# STM.net
KiCad netlist of a schematic drawn in Altium Designer
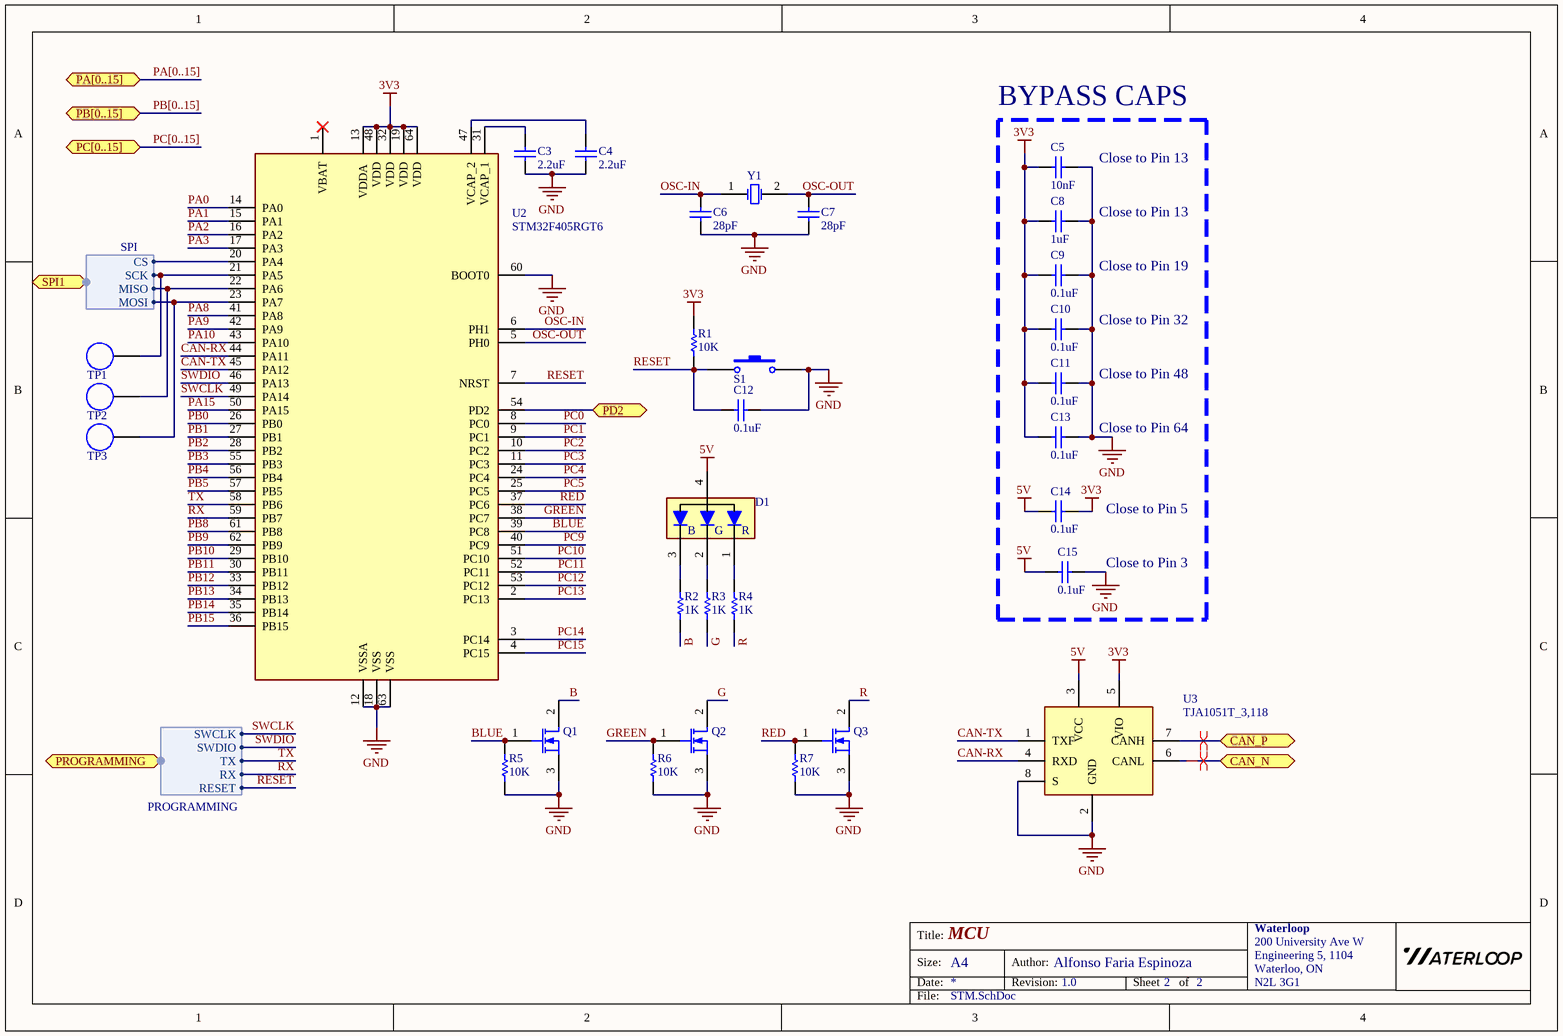
[diagram p0: STM.SchDoc]

(export (version "E")
  (design (tool "Eeschema 10.0.6"))
  (components
    (comp (ref "C3")
      (value "2.2uF")
      (footprint "0805 - Capacitor")
      (description "Nonpolarized Capacitor")
      (fields
        (field (name "MANUFACTURER") "Samsung")
        (field (name "MANUFACTURER PART NUMBER") "CL21B225KPFNNNE")
      )
      (libsource (lib "General") (part "Capacitor - Nonpolarized"))
    )
    (comp (ref "C4")
      (value "2.2uF")
      (footprint "0805 - Capacitor")
      (description "Nonpolarized Capacitor")
      (fields
        (field (name "MANUFACTURER") "Samsung")
        (field (name "MANUFACTURER PART NUMBER") "CL21B225KPFNNNE")
      )
      (libsource (lib "General") (part "Capacitor - Nonpolarized"))
    )
    (comp (ref "C5")
      (value "10nF")
      (footprint "0805 - Capacitor")
      (description "Nonpolarized Capacitor")
      (fields
        (field (name "MANUFACTURER") "Yageo")
        (field (name "MANUFACTURER PART NUMBER") "CC0805KRX7R9BB103")
      )
      (libsource (lib "General") (part "Capacitor - Nonpolarized"))
    )
    (comp (ref "C6")
      (value "28pF")
      (footprint "0805 - Capacitor")
      (description "Nonpolarized Capacitor")
      (fields
        (field (name "MANUFACTURER") "Samsung")
        (field (name "MANUFACTURER PART NUMBER") "CL21C270JCANNNC")
      )
      (libsource (lib "General") (part "Capacitor - Nonpolarized"))
    )
    (comp (ref "C7")
      (value "28pF")
      (footprint "0805 - Capacitor")
      (description "Nonpolarized Capacitor")
      (fields
        (field (name "MANUFACTURER") "Samsung")
        (field (name "MANUFACTURER PART NUMBER") "CL21C270JCANNNC")
      )
      (libsource (lib "General") (part "Capacitor - Nonpolarized"))
    )
    (comp (ref "C8")
      (value "1uF")
      (footprint "0805 - Capacitor")
      (description "Nonpolarized Capacitor")
      (fields
        (field (name "MANUFACTURER") "Yageo")
        (field (name "MANUFACTURER PART NUMBER") "CC0805KKX7R9BB105")
      )
      (libsource (lib "General") (part "Capacitor - Nonpolarized"))
    )
    (comp (ref "C9")
      (value "0.1uF")
      (footprint "0805 - Capacitor")
      (description "Nonpolarized Capacitor")
      (fields
        (field (name "MANUFACTURER") "Yageo")
        (field (name "MANUFACTURER PART NUMBER") "CC0805KRX7R9BB104")
      )
      (libsource (lib "General") (part "Capacitor - Nonpolarized"))
    )
    (comp (ref "C10")
      (value "0.1uF")
      (footprint "0805 - Capacitor")
      (description "Nonpolarized Capacitor")
      (fields
        (field (name "MANUFACTURER") "Yageo")
        (field (name "MANUFACTURER PART NUMBER") "CC0805KRX7R9BB104")
      )
      (libsource (lib "General") (part "Capacitor - Nonpolarized"))
    )
    (comp (ref "C11")
      (value "0.1uF")
      (footprint "0805 - Capacitor")
      (description "Nonpolarized Capacitor")
      (fields
        (field (name "MANUFACTURER") "Yageo")
        (field (name "MANUFACTURER PART NUMBER") "CC0805KRX7R9BB104")
      )
      (libsource (lib "General") (part "Capacitor - Nonpolarized"))
    )
    (comp (ref "C12")
      (value "0.1uF")
      (footprint "0805 - Capacitor")
      (description "Nonpolarized Capacitor")
      (fields
        (field (name "MANUFACTURER") "Yageo")
        (field (name "MANUFACTURER PART NUMBER") "CC0805KRX7R9BB104")
      )
      (libsource (lib "General") (part "Capacitor - Nonpolarized"))
    )
    (comp (ref "C13")
      (value "0.1uF")
      (footprint "0805 - Capacitor")
      (description "Nonpolarized Capacitor")
      (fields
        (field (name "MANUFACTURER") "Yageo")
        (field (name "MANUFACTURER PART NUMBER") "CC0805KRX7R9BB104")
      )
      (libsource (lib "General") (part "Capacitor - Nonpolarized"))
    )
    (comp (ref "C14")
      (value "0.1uF")
      (footprint "0805 - Capacitor")
      (description "Nonpolarized Capacitor")
      (fields
        (field (name "MANUFACTURER") "Yageo")
        (field (name "MANUFACTURER PART NUMBER") "CC0805KRX7R9BB104")
      )
      (libsource (lib "General") (part "Capacitor - Nonpolarized"))
    )
    (comp (ref "C15")
      (value "0.1uF")
      (footprint "0805 - Capacitor")
      (description "Nonpolarized Capacitor")
      (fields
        (field (name "MANUFACTURER") "Yageo")
        (field (name "MANUFACTURER PART NUMBER") "CC0805KRX7R9BB104")
      )
      (libsource (lib "General") (part "Capacitor - Nonpolarized"))
    )
    (comp (ref "D1")
      (value "RGB LED- Common Anode")
      (footprint "4-PLCC RGB LED")
      (fields
        (field (name "MANUFACTURER PART NUMBER") "AAA3528LSEEZGKQBKS")
        (field (name "MANUFACTURER") "Kingbright")
      )
      (libsource (lib "General") (part "RGB LED- Common Anode"))
    )
    (comp (ref "Q1")
      (value "MOSFET-N")
      (footprint "SC70/SOT323")
      (description "N-Channel MOSFET")
      (fields (field (name "MANUFACTURER PART NUMBER") "NVS4409NT1G") (field (name "MANUFACTURER") "ON SEMI"))
      (libsource (lib "General") (part "MOSFET-N"))
    )
    (comp (ref "Q2")
      (value "MOSFET-N")
      (footprint "SC70/SOT323")
      (description "N-Channel MOSFET")
      (fields (field (name "MANUFACTURER PART NUMBER") "NVS4409NT1G") (field (name "MANUFACTURER") "ON SEMI"))
      (libsource (lib "General") (part "MOSFET-N"))
    )
    (comp (ref "Q3")
      (value "MOSFET-N")
      (footprint "SC70/SOT323")
      (description "N-Channel MOSFET")
      (fields (field (name "MANUFACTURER PART NUMBER") "NVS4409NT1G") (field (name "MANUFACTURER") "ON SEMI"))
      (libsource (lib "General") (part "MOSFET-N"))
    )
    (comp (ref "R1")
      (value "10K")
      (footprint "0603 - Resistor")
      (description "Resistor")
      (fields
        (field (name "MANUFACTURER PART NUMBER") "RC0603FR-0710KL")
        (field (name "MANUFACTURER") "Yageo")
      )
      (libsource (lib "General") (part "Resistor"))
    )
    (comp (ref "R2")
      (value "1K")
      (footprint "0603 - Resistor")
      (description "Resistor")
      (fields
        (field (name "MANUFACTURER PART NUMBER") "RC0603FR-071KL")
        (field (name "MANUFACTURER") "Yageo")
      )
      (libsource (lib "General") (part "Resistor"))
    )
    (comp (ref "R3")
      (value "1K")
      (footprint "0603 - Resistor")
      (description "Resistor")
      (fields
        (field (name "MANUFACTURER PART NUMBER") "RC0603FR-071KL")
        (field (name "MANUFACTURER") "Yageo")
      )
      (libsource (lib "General") (part "Resistor"))
    )
    (comp (ref "R4")
      (value "1K")
      (footprint "0603 - Resistor")
      (description "Resistor")
      (fields
        (field (name "MANUFACTURER PART NUMBER") "RC0603FR-071KL")
        (field (name "MANUFACTURER") "Yageo")
      )
      (libsource (lib "General") (part "Resistor"))
    )
    (comp (ref "R5")
      (value "10K")
      (footprint "0603 - Resistor")
      (description "Resistor")
      (fields
        (field (name "MANUFACTURER PART NUMBER") "RC0603FR-0710KL")
        (field (name "MANUFACTURER") "Yageo")
      )
      (libsource (lib "General") (part "Resistor"))
    )
    (comp (ref "R6")
      (value "10K")
      (footprint "0603 - Resistor")
      (description "Resistor")
      (fields
        (field (name "MANUFACTURER PART NUMBER") "RC0603FR-0710KL")
        (field (name "MANUFACTURER") "Yageo")
      )
      (libsource (lib "General") (part "Resistor"))
    )
    (comp (ref "R7")
      (value "10K")
      (footprint "0603 - Resistor")
      (description "Resistor")
      (fields
        (field (name "MANUFACTURER PART NUMBER") "RC0603FR-0710KL")
        (field (name "MANUFACTURER") "Yageo")
      )
      (libsource (lib "General") (part "Resistor"))
    )
    (comp (ref "S1")
      (value "Switch - Push Button")
      (footprint "6x6mm Switch")
      (description "Push Button Switch")
      (fields (field (name "MANUFACTURER PART NUMBER") "1301.9315") (field (name "MANUFACTURER") "Schurter"))
      (libsource (lib "General") (part "Switch - Push Button"))
    )
    (comp (ref "TP1")
      (value "CLOCK")
      (footprint "Test Point")
      (description "Test Point")
      (libsource (lib "General") (part "Test Point"))
    )
    (comp (ref "TP2")
      (value "MISO")
      (footprint "Test Point")
      (description "Test Point")
      (libsource (lib "General") (part "Test Point"))
    )
    (comp (ref "TP3")
      (value "MOSI")
      (footprint "Test Point")
      (description "Test Point")
      (libsource (lib "General") (part "Test Point"))
    )
    (comp (ref "U2")
      (value "STM32F405RGT6")
      (footprint "STM32F405RG")
      (description "ST 64-pin Micro")
      (fields (field (name "MANUFACTURER PART NUMBER") "STM32F405RGT7") (field (name "MANUFACTURER") "ST"))
      (libsource (lib "GeneralComponents") (part "STM32F405RGT6"))
    )
    (comp (ref "U3")
      (value "TJA1051T_3,118")
      (footprint "TJA1051T/3,118")
      (description "CAN Transceiver IC 4.5V-5.5V 250ns")
      (fields (field (name "MANUFACTURER") "NXP") (field (name "MANUFACTURER PART NUMBER") "TJA1051T/3,118"))
      (libsource (lib "GeneralComponents") (part "TJA1051T_3,118"))
    )
    (comp (ref "Y1")
      (value "Oscillator")
      (footprint "2-SMD NO LEAD CRSYSTAL")
      (description "Crystal Oscillator")
      (fields
        (field (name "MANUFACTURER PART NUMBER") "ABM3-16.000MHZ-B2-T")
        (field (name "MANUFACTURER") "Abracon")
      )
      (libsource (lib "General") (part "Oscillator"))
    )
  )
  (nets
    (net (code "16") (name "/B") (class "Default")
      (node (ref "Q1") (pin "2") (pinfunction "D_2") (pintype "passive"))
      (node (ref "R2") (pin "1") (pinfunction "1_1") (pintype "passive"))
    )
    (net (code "17") (name "/BLUE") (class "Default")
      (node (ref "Q1") (pin "1") (pinfunction "G_1") (pintype "passive"))
      (node (ref "R5") (pin "2") (pinfunction "2_2") (pintype "passive"))
      (node (ref "U2") (pin "39") (pinfunction "PC8_39") (pintype "passive"))
    )
    (net (code "18") (name "/CAN-RX") (class "Default")
      (node (ref "U2") (pin "44") (pinfunction "PA11_44") (pintype "passive"))
      (node (ref "U3") (pin "4") (pinfunction "RXD_4") (pintype "passive"))
    )
    (net (code "19") (name "/CAN-TX") (class "Default")
      (node (ref "U2") (pin "45") (pinfunction "PA12_45") (pintype "passive"))
      (node (ref "U3") (pin "1") (pinfunction "TXF_1") (pintype "passive"))
    )
    (net (code "20") (name "/CAN_N") (class "Default")
      (node (ref "U3") (pin "6") (pinfunction "CANL_6") (pintype "passive"))
    )
    (net (code "21") (name "/CAN_P") (class "Default")
      (node (ref "U3") (pin "7") (pinfunction "CANH_7") (pintype "passive"))
    )
    (net (code "22") (name "/CS") (class "Default")
      (node (ref "U2") (pin "20") (pinfunction "PA4_20") (pintype "passive"))
    )
    (net (code "23") (name "/G") (class "Default")
      (node (ref "Q2") (pin "2") (pinfunction "D_2") (pintype "passive"))
      (node (ref "R3") (pin "1") (pinfunction "1_1") (pintype "passive"))
    )
    (net (code "24") (name "/GREEN") (class "Default")
      (node (ref "Q2") (pin "1") (pinfunction "G_1") (pintype "passive"))
      (node (ref "R6") (pin "2") (pinfunction "2_2") (pintype "passive"))
      (node (ref "U2") (pin "38") (pinfunction "PC7_38") (pintype "passive"))
    )
    (net (code "25") (name "/MISO") (class "Default")
      (node (ref "TP2") (pin "0") (pinfunction "0_0") (pintype "passive"))
      (node (ref "U2") (pin "22") (pinfunction "PA6_22") (pintype "passive"))
    )
    (net (code "26") (name "/MOSI") (class "Default")
      (node (ref "TP3") (pin "0") (pinfunction "0_0") (pintype "passive"))
      (node (ref "U2") (pin "23") (pinfunction "PA7_23") (pintype "passive"))
    )
    (net (code "27") (name "/OSC-IN") (class "Default")
      (node (ref "C6") (pin "2") (pinfunction "2_2") (pintype "passive"))
      (node (ref "U2") (pin "6") (pinfunction "PH1_6") (pintype "passive"))
      (node (ref "Y1") (pin "1") (pinfunction "OSC1_1") (pintype "passive"))
    )
    (net (code "28") (name "/OSC-OUT") (class "Default")
      (node (ref "C7") (pin "2") (pinfunction "2_2") (pintype "passive"))
      (node (ref "U2") (pin "5") (pinfunction "PH0_5") (pintype "passive"))
      (node (ref "Y1") (pin "2") (pinfunction "OSC2_2") (pintype "passive"))
    )
    (net (code "29") (name "/PA0") (class "Default")
      (node (ref "U2") (pin "14") (pinfunction "PA0_14") (pintype "passive"))
    )
    (net (code "30") (name "/PA1") (class "Default")
      (node (ref "U2") (pin "15") (pinfunction "PA1_15") (pintype "passive"))
    )
    (net (code "31") (name "/PA2") (class "Default")
      (node (ref "U2") (pin "16") (pinfunction "PA2_16") (pintype "passive"))
    )
    (net (code "32") (name "/PA3") (class "Default")
      (node (ref "U2") (pin "17") (pinfunction "PA3_17") (pintype "passive"))
    )
    (net (code "33") (name "/PA8") (class "Default")
      (node (ref "U2") (pin "41") (pinfunction "PA8_41") (pintype "passive"))
    )
    (net (code "34") (name "/PA9") (class "Default")
      (node (ref "U2") (pin "42") (pinfunction "PA9_42") (pintype "passive"))
    )
    (net (code "35") (name "/PA10") (class "Default")
      (node (ref "U2") (pin "43") (pinfunction "PA10_43") (pintype "passive"))
    )
    (net (code "36") (name "/PA15") (class "Default")
      (node (ref "U2") (pin "50") (pinfunction "PA15_50") (pintype "passive"))
    )
    (net (code "38") (name "/PB0") (class "Default")
      (node (ref "U2") (pin "26") (pinfunction "PB0_26") (pintype "passive"))
    )
    (net (code "39") (name "/PB1") (class "Default")
      (node (ref "U2") (pin "27") (pinfunction "PB1_27") (pintype "passive"))
    )
    (net (code "40") (name "/PB2") (class "Default")
      (node (ref "U2") (pin "28") (pinfunction "PB2_28") (pintype "passive"))
    )
    (net (code "41") (name "/PB3") (class "Default")
      (node (ref "U2") (pin "55") (pinfunction "PB3_55") (pintype "passive"))
    )
    (net (code "42") (name "/PB4") (class "Default")
      (node (ref "U2") (pin "56") (pinfunction "PB4_56") (pintype "passive"))
    )
    (net (code "43") (name "/PB5") (class "Default")
      (node (ref "U2") (pin "57") (pinfunction "PB5_57") (pintype "passive"))
    )
    (net (code "44") (name "/PB8") (class "Default")
      (node (ref "U2") (pin "61") (pinfunction "PB8_61") (pintype "passive"))
    )
    (net (code "45") (name "/PB9") (class "Default")
      (node (ref "U2") (pin "62") (pinfunction "PB9_62") (pintype "passive"))
    )
    (net (code "46") (name "/PB10") (class "Default")
      (node (ref "U2") (pin "29") (pinfunction "PB10_29") (pintype "passive"))
    )
    (net (code "47") (name "/PB11") (class "Default")
      (node (ref "U2") (pin "30") (pinfunction "PB11_30") (pintype "passive"))
    )
    (net (code "48") (name "/PB12") (class "Default")
      (node (ref "U2") (pin "33") (pinfunction "PB12_33") (pintype "passive"))
    )
    (net (code "49") (name "/PB13") (class "Default")
      (node (ref "U2") (pin "34") (pinfunction "PB13_34") (pintype "passive"))
    )
    (net (code "50") (name "/PB14") (class "Default")
      (node (ref "U2") (pin "35") (pinfunction "PB14_35") (pintype "passive"))
    )
    (net (code "51") (name "/PB15") (class "Default")
      (node (ref "U2") (pin "36") (pinfunction "PB15_36") (pintype "passive"))
    )
    (net (code "53") (name "/PC0") (class "Default")
      (node (ref "U2") (pin "8") (pinfunction "PC0_8") (pintype "passive"))
    )
    (net (code "54") (name "/PC1") (class "Default")
      (node (ref "U2") (pin "9") (pinfunction "PC1_9") (pintype "passive"))
    )
    (net (code "55") (name "/PC2") (class "Default")
      (node (ref "U2") (pin "10") (pinfunction "PC2_10") (pintype "passive"))
    )
    (net (code "56") (name "/PC3") (class "Default")
      (node (ref "U2") (pin "11") (pinfunction "PC3_11") (pintype "passive"))
    )
    (net (code "57") (name "/PC4") (class "Default")
      (node (ref "U2") (pin "24") (pinfunction "PC4_24") (pintype "passive"))
    )
    (net (code "58") (name "/PC5") (class "Default")
      (node (ref "U2") (pin "25") (pinfunction "PC5_25") (pintype "passive"))
    )
    (net (code "59") (name "/PC9") (class "Default")
      (node (ref "U2") (pin "40") (pinfunction "PC9_40") (pintype "passive"))
    )
    (net (code "60") (name "/PC10") (class "Default")
      (node (ref "U2") (pin "51") (pinfunction "PC10_51") (pintype "passive"))
    )
    (net (code "61") (name "/PC11") (class "Default")
      (node (ref "U2") (pin "52") (pinfunction "PC11_52") (pintype "passive"))
    )
    (net (code "62") (name "/PC12") (class "Default")
      (node (ref "U2") (pin "53") (pinfunction "PC12_53") (pintype "passive"))
    )
    (net (code "63") (name "/PC13") (class "Default")
      (node (ref "U2") (pin "2") (pinfunction "PC13_2") (pintype "passive"))
    )
    (net (code "64") (name "/PC14") (class "Default")
      (node (ref "U2") (pin "3") (pinfunction "PC14_3") (pintype "passive"))
    )
    (net (code "65") (name "/PC15") (class "Default")
      (node (ref "U2") (pin "4") (pinfunction "PC15_4") (pintype "passive"))
    )
    (net (code "67") (name "/PD2") (class "Default")
      (node (ref "U2") (pin "54") (pinfunction "PD2_54") (pintype "passive"))
    )
    (net (code "68") (name "/R") (class "Default")
      (node (ref "Q3") (pin "2") (pinfunction "D_2") (pintype "passive"))
      (node (ref "R4") (pin "1") (pinfunction "1_1") (pintype "passive"))
    )
    (net (code "69") (name "/RED") (class "Default")
      (node (ref "Q3") (pin "1") (pinfunction "G_1") (pintype "passive"))
      (node (ref "R7") (pin "2") (pinfunction "2_2") (pintype "passive"))
      (node (ref "U2") (pin "37") (pinfunction "PC6_37") (pintype "passive"))
    )
    (net (code "70") (name "/RESET") (class "Default")
      (node (ref "C12") (pin "1") (pinfunction "1_1") (pintype "passive"))
      (node (ref "R1") (pin "1") (pinfunction "1_1") (pintype "passive"))
      (node (ref "S1") (pin "1") (pinfunction "1_1") (pintype "passive"))
      (node (ref "U2") (pin "7") (pinfunction "NRST_7") (pintype "passive"))
    )
    (net (code "71") (name "/RX") (class "Default")
      (node (ref "U2") (pin "59") (pinfunction "PB7_59") (pintype "passive"))
    )
    (net (code "72") (name "/SCK") (class "Default")
      (node (ref "TP1") (pin "0") (pinfunction "0_0") (pintype "passive"))
      (node (ref "U2") (pin "21") (pinfunction "PA5_21") (pintype "passive"))
    )
    (net (code "73") (name "/SWCLK") (class "Default")
      (node (ref "U2") (pin "49") (pinfunction "PA14_49") (pintype "passive"))
    )
    (net (code "74") (name "/SWDIO") (class "Default")
      (node (ref "U2") (pin "46") (pinfunction "PA13_46") (pintype "passive"))
    )
    (net (code "75") (name "/TX") (class "Default")
      (node (ref "U2") (pin "58") (pinfunction "PB6_58") (pintype "passive"))
    )
    (net (code "78") (name "3V3") (class "Default")
      (node (ref "C10") (pin "1") (pinfunction "1_1") (pintype "passive"))
      (node (ref "C11") (pin "1") (pinfunction "1_1") (pintype "passive"))
      (node (ref "C13") (pin "1") (pinfunction "1_1") (pintype "passive"))
      (node (ref "C14") (pin "1") (pinfunction "1_1") (pintype "passive"))
      (node (ref "C5") (pin "1") (pinfunction "1_1") (pintype "passive"))
      (node (ref "C8") (pin "1") (pinfunction "1_1") (pintype "passive"))
      (node (ref "C9") (pin "1") (pinfunction "1_1") (pintype "passive"))
      (node (ref "R1") (pin "2") (pinfunction "2_2") (pintype "passive"))
      (node (ref "U2") (pin "13") (pinfunction "VDDA_13") (pintype "power_in"))
      (node (ref "U2") (pin "19") (pinfunction "VDD_19") (pintype "power_in"))
      (node (ref "U2") (pin "32") (pinfunction "VDD_32") (pintype "power_in"))
      (node (ref "U2") (pin "48") (pinfunction "VDD_48") (pintype "power_in"))
      (node (ref "U2") (pin "64") (pinfunction "VDD_64") (pintype "power_in"))
      (node (ref "U3") (pin "5") (pinfunction "VIO_5") (pintype "passive"))
    )
    (net (code "79") (name "5V") (class "Default")
      (node (ref "C14") (pin "2") (pinfunction "2_2") (pintype "passive"))
      (node (ref "C15") (pin "2") (pinfunction "2_2") (pintype "passive"))
      (node (ref "D1") (pin "4") (pinfunction "11_4") (pintype "passive"))
      (node (ref "U3") (pin "3") (pinfunction "VCC_3") (pintype "passive"))
    )
    (net (code "80") (name "GND") (class "Default")
      (node (ref "C10") (pin "2") (pinfunction "2_2") (pintype "passive"))
      (node (ref "C11") (pin "2") (pinfunction "2_2") (pintype "passive"))
      (node (ref "C12") (pin "2") (pinfunction "2_2") (pintype "passive"))
      (node (ref "C13") (pin "2") (pinfunction "2_2") (pintype "passive"))
      (node (ref "C15") (pin "1") (pinfunction "1_1") (pintype "passive"))
      (node (ref "C3") (pin "1") (pinfunction "1_1") (pintype "passive"))
      (node (ref "C4") (pin "1") (pinfunction "1_1") (pintype "passive"))
      (node (ref "C5") (pin "2") (pinfunction "2_2") (pintype "passive"))
      (node (ref "C6") (pin "1") (pinfunction "1_1") (pintype "passive"))
      (node (ref "C7") (pin "1") (pinfunction "1_1") (pintype "passive"))
      (node (ref "C8") (pin "2") (pinfunction "2_2") (pintype "passive"))
      (node (ref "C9") (pin "2") (pinfunction "2_2") (pintype "passive"))
      (node (ref "Q1") (pin "3") (pinfunction "S_3") (pintype "passive"))
      (node (ref "Q2") (pin "3") (pinfunction "S_3") (pintype "passive"))
      (node (ref "Q3") (pin "3") (pinfunction "S_3") (pintype "passive"))
      (node (ref "R5") (pin "1") (pinfunction "1_1") (pintype "passive"))
      (node (ref "R6") (pin "1") (pinfunction "1_1") (pintype "passive"))
      (node (ref "R7") (pin "1") (pinfunction "1_1") (pintype "passive"))
      (node (ref "S1") (pin "2") (pinfunction "2_2") (pintype "passive"))
      (node (ref "U2") (pin "12") (pinfunction "VSSA_12") (pintype "power_in"))
      (node (ref "U2") (pin "18") (pinfunction "VSS_18") (pintype "power_in"))
      (node (ref "U2") (pin "60") (pinfunction "BOOT0_60") (pintype "passive"))
      (node (ref "U2") (pin "63") (pinfunction "VSS_63") (pintype "power_in"))
      (node (ref "U3") (pin "2") (pinfunction "GND_2") (pintype "passive"))
      (node (ref "U3") (pin "8") (pinfunction "S_8") (pintype "passive"))
    )
    (net (code "81") (name "Net-(D1-11-Pad1)") (class "Default")
      (node (ref "D1") (pin "1") (pinfunction "11_1") (pintype "passive"))
      (node (ref "R4") (pin "2") (pinfunction "2_2") (pintype "passive"))
    )
    (net (code "82") (name "Net-(D1-11-Pad2)") (class "Default")
      (node (ref "D1") (pin "2") (pinfunction "11_2") (pintype "passive"))
      (node (ref "R3") (pin "2") (pinfunction "2_2") (pintype "passive"))
    )
    (net (code "83") (name "Net-(D1-11-Pad3)") (class "Default")
      (node (ref "D1") (pin "3") (pinfunction "11_3") (pintype "passive"))
      (node (ref "R2") (pin "2") (pinfunction "2_2") (pintype "passive"))
    )
    (net (code "84") (name "Net-(U2-VCAP_1)") (class "Default")
      (node (ref "C3") (pin "2") (pinfunction "2_2") (pintype "passive"))
      (node (ref "U2") (pin "31") (pinfunction "VCAP_1_31") (pintype "power_in"))
    )
    (net (code "85") (name "Net-(U2-VCAP_2)") (class "Default")
      (node (ref "C4") (pin "2") (pinfunction "2_2") (pintype "passive"))
      (node (ref "U2") (pin "47") (pinfunction "VCAP_2_47") (pintype "power_in"))
    )
    (net (code "86") (name "unconnected-(U2-VBAT-Pad1)") (class "Default")
      (node (ref "U2") (pin "1") (pinfunction "VBAT_1") (pintype "power_in+no_connect"))
    )
  )
)
